# Shift_Registers.net
KiCad netlist of a schematic drawn in Altium Designer
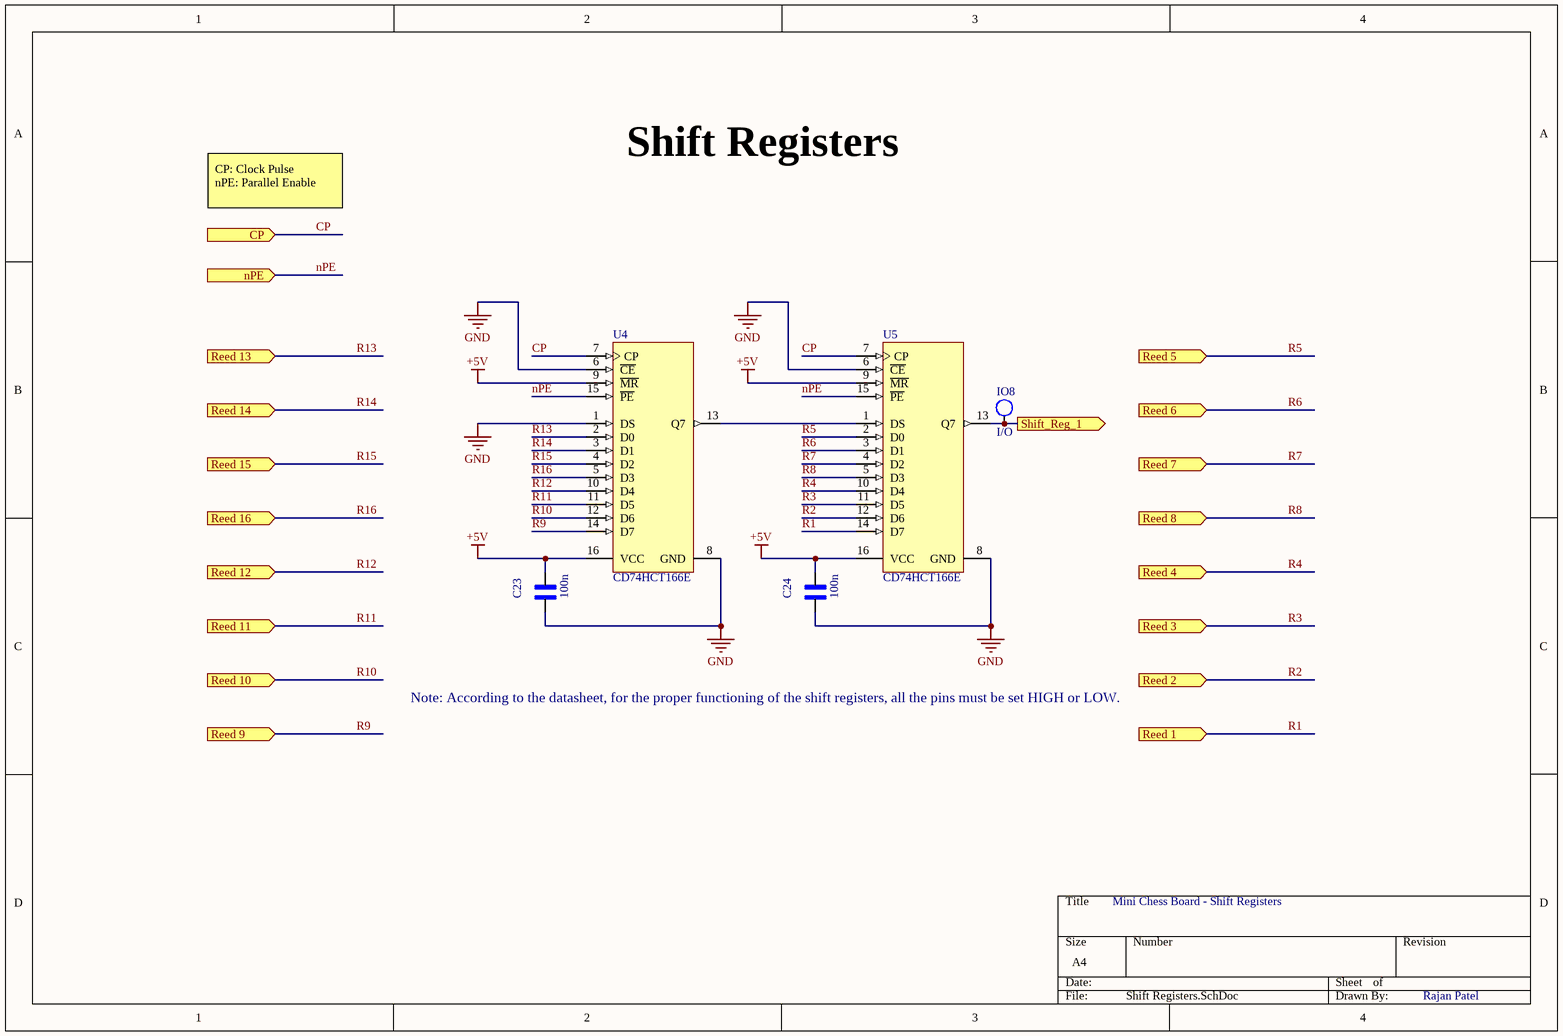
[diagram p0: Shift Registers.SchDoc]

(export (version "E")
  (design (tool "Eeschema 10.0.6"))
  (components
    (comp (ref "C23")
      (value "100n")
      (footprint "CAP 0805")
      (libsource (lib "MiniChessBoardSchLib") (part "CAP 0805"))
    )
    (comp (ref "C24")
      (value "100n")
      (footprint "CAP 0805")
      (libsource (lib "MiniChessBoardSchLib") (part "CAP 0805"))
    )
    (comp (ref "IO8") (value "I/O") (footprint "I/O") (libsource (lib "MiniChessBoardSchLib") (part "I/O")))
    (comp (ref "U4")
      (value "CD74HCT166E")
      (footprint "N0016A")
      (description "High Speed CMOS Logic 8-Bit Parallel-In/Serial-Out Shift Register, N0016A, TUBE")
      (fields
        (field (name "MANUFACTURER") "Texas Instruments")
        (field (name "GENERIC PART NUMBER") "CD74HCT166")
      )
      (libsource (lib "Altium Content Vault") (part "TI-CDX4HCX166-16"))
    )
    (comp (ref "U5")
      (value "CD74HCT166E")
      (footprint "N0016A")
      (description "High Speed CMOS Logic 8-Bit Parallel-In/Serial-Out Shift Register, N0016A, TUBE")
      (fields
        (field (name "MANUFACTURER") "Texas Instruments")
        (field (name "GENERIC PART NUMBER") "CD74HCT166")
      )
      (libsource (lib "Altium Content Vault") (part "TI-CDX4HCX166-16"))
    )
  )
  (nets
    (net (code "1") (name "+5V") (class "Default")
      (node (ref "C23") (pin "2") (pinfunction "2_2") (pintype "passive"))
      (node (ref "C24") (pin "2") (pinfunction "2_2") (pintype "passive"))
      (node (ref "U4") (pin "16") (pinfunction "VCC_16") (pintype "power_in"))
      (node (ref "U4") (pin "9") (pinfunction "~{MR}_9") (pintype "input"))
      (node (ref "U5") (pin "16") (pinfunction "VCC_16") (pintype "power_in"))
      (node (ref "U5") (pin "9") (pinfunction "~{MR}_9") (pintype "input"))
    )
    (net (code "2") (name "/CP") (class "Default")
      (node (ref "U4") (pin "7") (pinfunction "CP_7") (pintype "input"))
      (node (ref "U5") (pin "7") (pinfunction "CP_7") (pintype "input"))
    )
    (net (code "3") (name "/R1") (class "Default")
      (node (ref "U5") (pin "14") (pinfunction "D7_14") (pintype "input"))
    )
    (net (code "4") (name "/R2") (class "Default")
      (node (ref "U5") (pin "12") (pinfunction "D6_12") (pintype "input"))
    )
    (net (code "5") (name "/R3") (class "Default")
      (node (ref "U5") (pin "11") (pinfunction "D5_11") (pintype "input"))
    )
    (net (code "6") (name "/R4") (class "Default")
      (node (ref "U5") (pin "10") (pinfunction "D4_10") (pintype "input"))
    )
    (net (code "7") (name "/R5") (class "Default")
      (node (ref "U5") (pin "2") (pinfunction "D0_2") (pintype "input"))
    )
    (net (code "8") (name "/R6") (class "Default")
      (node (ref "U5") (pin "3") (pinfunction "D1_3") (pintype "input"))
    )
    (net (code "9") (name "/R7") (class "Default")
      (node (ref "U5") (pin "4") (pinfunction "D2_4") (pintype "input"))
    )
    (net (code "10") (name "/R8") (class "Default")
      (node (ref "U5") (pin "5") (pinfunction "D3_5") (pintype "input"))
    )
    (net (code "11") (name "/R9") (class "Default")
      (node (ref "U4") (pin "14") (pinfunction "D7_14") (pintype "input"))
    )
    (net (code "12") (name "/R10") (class "Default")
      (node (ref "U4") (pin "12") (pinfunction "D6_12") (pintype "input"))
    )
    (net (code "13") (name "/R11") (class "Default")
      (node (ref "U4") (pin "11") (pinfunction "D5_11") (pintype "input"))
    )
    (net (code "14") (name "/R12") (class "Default")
      (node (ref "U4") (pin "10") (pinfunction "D4_10") (pintype "input"))
    )
    (net (code "15") (name "/R13") (class "Default")
      (node (ref "U4") (pin "2") (pinfunction "D0_2") (pintype "input"))
    )
    (net (code "16") (name "/R14") (class "Default")
      (node (ref "U4") (pin "3") (pinfunction "D1_3") (pintype "input"))
    )
    (net (code "17") (name "/R15") (class "Default")
      (node (ref "U4") (pin "4") (pinfunction "D2_4") (pintype "input"))
    )
    (net (code "18") (name "/R16") (class "Default")
      (node (ref "U4") (pin "5") (pinfunction "D3_5") (pintype "input"))
    )
    (net (code "19") (name "/Shift_Reg_1") (class "Default")
      (node (ref "IO8") (pin "1") (pinfunction "1_1") (pintype "passive"))
      (node (ref "U5") (pin "13") (pinfunction "Q7_13") (pintype "output"))
    )
    (net (code "20") (name "/nPE") (class "Default")
      (node (ref "U4") (pin "15") (pinfunction "~{PE}_15") (pintype "input"))
      (node (ref "U5") (pin "15") (pinfunction "~{PE}_15") (pintype "input"))
    )
    (net (code "21") (name "GND") (class "Default")
      (node (ref "C23") (pin "1") (pinfunction "1_1") (pintype "passive"))
      (node (ref "C24") (pin "1") (pinfunction "1_1") (pintype "passive"))
      (node (ref "U4") (pin "1") (pinfunction "DS_1") (pintype "input"))
      (node (ref "U4") (pin "6") (pinfunction "~{CE}_6") (pintype "input"))
      (node (ref "U4") (pin "8") (pinfunction "GND_8") (pintype "power_in"))
      (node (ref "U5") (pin "6") (pinfunction "~{CE}_6") (pintype "input"))
      (node (ref "U5") (pin "8") (pinfunction "GND_8") (pintype "power_in"))
    )
    (net (code "22") (name "Net-(U4-Q7)") (class "Default")
      (node (ref "U4") (pin "13") (pinfunction "Q7_13") (pintype "output"))
      (node (ref "U5") (pin "1") (pinfunction "DS_1") (pintype "input"))
    )
  )
)
